# Power.net
KiCad netlist of a schematic drawn in Altium Designer
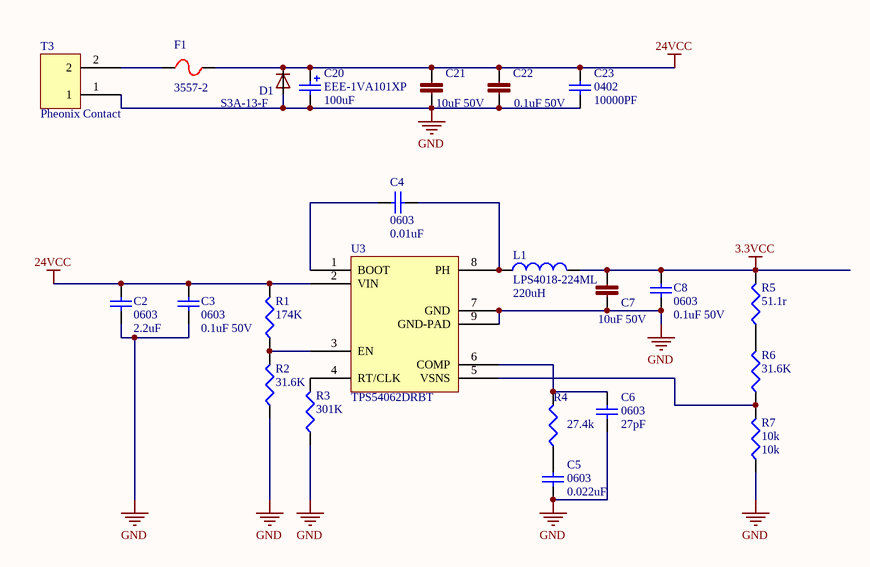
[diagram p0: Power.SchDoc]

(export (version "E")
  (design (tool "Eeschema 10.0.6"))
  (components
    (comp (ref "C2")
      (value "0603")
      (footprint "C0805")
      (description "CAP CER 2.2UF 50V 10% X5R 0805")
      (fields
        (field (name "MFR PART #") "CL21A225KB9LNNC")
        (field (name "MFR") "Samsung")
        (field (name "ALTIUM_VALUE") "2.2uF")
      )
      (libsource (lib "MongoosMini") (part "CL21A225KB9LNNC"))
    )
    (comp (ref "C3")
      (value "0603")
      (footprint "C0603")
      (description "CAP CER 0.1UF 50V 10% X7R 0603")
      (fields
        (field (name "MFR PART #") "CL10B104KB8SFNC")
        (field (name "MFR") "Samsung")
        (field (name "ALTIUM_VALUE") "0.1uF 50V")
      )
      (libsource (lib "MongoosMini") (part "CL10B104KB8SFNC"))
    )
    (comp (ref "C4")
      (value "0603")
      (footprint "C0603")
      (description "CAP CER 10000PF 50V 10% X7R 0603")
      (fields
        (field (name "MFR PART #") "CL10B103KB8NCNC")
        (field (name "MFR") "Samsung")
        (field (name "ALTIUM_VALUE") "0.01uF")
      )
      (libsource (lib "MongoosMini") (part "CL10B103KB8NCNC"))
    )
    (comp (ref "C5")
      (value "0603")
      (footprint "C0603")
      (description "CAP CER 0.022UF 50V 5% X7R 0603")
      (fields
        (field (name "MFR PART #") "CL10B223JB8NNNC")
        (field (name "MFR") "Samsung")
        (field (name "ALTIUM_VALUE") "0.022uF")
      )
      (libsource (lib "MongoosMini") (part "CL10B223JB8NNNC"))
    )
    (comp (ref "C6")
      (value "0603")
      (footprint "C0603")
      (description "CAP CER 27PF 50V 5% NP0 0603")
      (fields
        (field (name "MFR PART #") "CL10C270JB8NNNC")
        (field (name "MFR") "Samsung")
        (field (name "ALTIUM_VALUE") "27pF")
      )
      (libsource (lib "MongoosMini") (part "CL10C270JB8NNNC"))
    )
    (comp (ref "C7")
      (value "10uF 50V")
      (footprint "C1206")
      (description "CAP CER 10UF 50V 10% X5R 1206")
      (fields
        (field (name "MANUFACTURER") "Samsung")
        (field (name "MANUFACTURERPARTNUMBER") "CL31A106KBHNNNE")
        (field (name "PUBLISHER") "UltiMachine")
      )
      (libsource (lib "Tigershark3D") (part "CL31A106KBHNNNE"))
    )
    (comp (ref "C8")
      (value "0603")
      (footprint "C0603")
      (description "CAP CER 0.1UF 50V 10% X7R 0603")
      (fields
        (field (name "MFR PART #") "CL10B104KB8SFNC")
        (field (name "MFR") "Samsung")
        (field (name "ALTIUM_VALUE") "0.1uF 50V")
      )
      (libsource (lib "MongoosMini") (part "CL10B104KB8SFNC"))
    )
    (comp (ref "C20")
      (value "EEE-1VA101XP")
      (footprint "EEE-1VA101XP")
      (description "CAP ALUM 100UF 35V 20% SMD")
      (fields (field (name "DIGIKEY PART #") "PCE3951CT-ND") (field (name "ALTIUM_VALUE") "100uF"))
      (libsource (lib "Tigershark3D") (part "EEE-1VA101XP"))
    )
    (comp (ref "C21")
      (value "10uF 50V")
      (footprint "C1206")
      (description "CAP CER 10UF 50V 10% X5R 1206")
      (fields
        (field (name "MANUFACTURER") "Samsung")
        (field (name "MANUFACTURERPARTNUMBER") "CL31A106KBHNNNE")
        (field (name "PUBLISHER") "UltiMachine")
      )
      (libsource (lib "Tigershark3D") (part "CL31A106KBHNNNE"))
    )
    (comp (ref "C22")
      (value "0.1uF 50V")
      (footprint "C0603")
      (description "CAP CER 0.1UF 50V 10% X7R 0603")
      (fields
        (field (name "MANUFACTURERPARTNUMBER") "CL10B104KB8SFNC")
        (field (name "PUBLISHER") "UltiMachine")
      )
      (libsource (lib "Tigershark3D") (part "CL10B104KB8SFNC"))
    )
    (comp (ref "C23")
      (value "10000PF")
      (footprint "C0402")
      (description "CAP CER 10000PF 50V 5% X7R 0402")
      (fields
        (field (name "MANUFACTURE PART #") "CL05B103JB5NNNC")
        (field (name "MANUFACTURER") "Samsung")
        (field (name "PACKAGEREFERENCE") "0402")
        (field (name "PUBLISHER") "Ultimachine")
      )
      (libsource (lib "Tigershark3D") (part "CL05B103JB5NNNC"))
    )
    (comp (ref "D1")
      (value "S3A-13-F")
      (footprint "DO-214AB")
      (description "DIODE DO-214AB")
      (fields (field (name "PUBLISHER") "UltiMachine"))
      (libsource (lib "3Delight") (part "S3A-13-F"))
    )
    (comp (ref "F1")
      (value "3557-2")
      (footprint "3557")
      (description "FUSE PTH ATO")
      (fields (field (name "PUBLISHER") "UltiMachine"))
      (libsource (lib "3Delight") (part "3557-2"))
    )
    (comp (ref "L1")
      (value "LPS4018-224ML")
      (footprint "LPS4018-224ML")
      (description "Inductor")
      (fields
        (field (name "MFR") "Coilcraft")
        (field (name "ALTIUM_VALUE") "220uH")
        (field (name "PUBLISHER") "Altium Limited")
      )
      (libsource (lib "MongoosMini") (part "LPS4018-224ML"))
    )
    (comp (ref "R1")
      (value "174K")
      (footprint "R0603")
      (description "RES SMD 174K OHM 1% 1/10W 0603")
      (fields (field (name "MFR") "Samsung"))
      (libsource (lib "MongoosMini") (part "RC1608F1743CS"))
    )
    (comp (ref "R2")
      (value "31.6K")
      (footprint "R0603")
      (description "RES SMD 31.6K OHM 1% 1/10W 0603")
      (fields (field (name "MFR") "Samsung"))
      (libsource (lib "MongoosMini") (part "RC1608F3162CS"))
    )
    (comp (ref "R3")
      (value "301K")
      (footprint "R0603")
      (description "RES SMD 301K OHM 1% 1/10W 0603")
      (fields (field (name "MFR") "Samsung"))
      (libsource (lib "MongoosMini") (part "RC1608F3013CS"))
    )
    (comp (ref "R4")
      (value "27.4k")
      (footprint "R0603")
      (description "RES SMD 27.4K OHM 1% 1/10W 0603")
      (fields (field (name "MFR") "Samsung"))
      (libsource (lib "MongoosMini") (part "RC1608F2742CS"))
    )
    (comp (ref "R5")
      (value "51.1r")
      (footprint "R0603")
      (description "RES SMD 51.1 OHM 1% 1/10W 0603")
      (fields (field (name "MFR") "Samsung"))
      (libsource (lib "MongoosMini") (part "RC1608F51R1CS"))
    )
    (comp (ref "R6")
      (value "31.6K")
      (footprint "R0603")
      (description "RES SMD 31.6K OHM 1% 1/10W 0603")
      (fields (field (name "MFR") "Samsung"))
      (libsource (lib "MongoosMini") (part "RC1608F3162CS"))
    )
    (comp (ref "R7")
      (value "10k")
      (footprint "R0603")
      (description "RES SMD 10K OHM 5% 1/10W 0603")
      (fields (field (name "MFR") "Samsung") (field (name "ALTIUM_VALUE") "10k"))
      (libsource (lib "MongoosMini") (part "RC1608J103CS"))
    )
    (comp (ref "T3")
      (value "Pheonix Contact")
      (footprint "CON-PHEONIX-508-Alt")
      (libsource (lib "Ribbon Breakout Schem Symbols") (part "Pheonix Contact 2X1"))
    )
    (comp (ref "U3")
      (value "TPS54062DRBT")
      (footprint "QFN65P300X300X100_HS-17N")
      (description "IC REG BUCK SYNC ADJ 50MA DRBT")
      (fields (field (name "MFR") "Texas Instruments"))
      (libsource (lib "MongoosMini") (part "TPS54062DRBT"))
    )
  )
  (nets
    (net (code "1") (name "3.3VCC") (class "Default")
      (node (ref "C7") (pin "1") (pinfunction "1_1") (pintype "passive"))
      (node (ref "C8") (pin "2") (pinfunction "2_2") (pintype "passive"))
      (node (ref "L1") (pin "2") (pinfunction "2_2") (pintype "passive"))
      (node (ref "R5") (pin "2") (pinfunction "2_2") (pintype "passive"))
    )
    (net (code "2") (name "24VCC") (class "Default")
      (node (ref "C2") (pin "2") (pinfunction "2_2") (pintype "passive"))
      (node (ref "C20") (pin "1") (pinfunction "1_1") (pintype "passive"))
      (node (ref "C21") (pin "1") (pinfunction "1_1") (pintype "passive"))
      (node (ref "C22") (pin "1") (pinfunction "1_1") (pintype "passive"))
      (node (ref "C23") (pin "2") (pinfunction "2_2") (pintype "passive"))
      (node (ref "C3") (pin "2") (pinfunction "2_2") (pintype "passive"))
      (node (ref "D1") (pin "C") (pinfunction "C_C") (pintype "passive"))
      (node (ref "F1") (pin "2") (pinfunction "2_2") (pintype "passive"))
      (node (ref "R1") (pin "2") (pinfunction "2_2") (pintype "passive"))
      (node (ref "U3") (pin "2") (pinfunction "VIN_2") (pintype "passive"))
    )
    (net (code "3") (name "GND") (class "Default")
      (node (ref "C2") (pin "1") (pinfunction "1_1") (pintype "passive"))
      (node (ref "C20") (pin "2") (pinfunction "2_2") (pintype "passive"))
      (node (ref "C21") (pin "2") (pinfunction "2_2") (pintype "passive"))
      (node (ref "C22") (pin "2") (pinfunction "2_2") (pintype "passive"))
      (node (ref "C23") (pin "1") (pinfunction "1_1") (pintype "passive"))
      (node (ref "C3") (pin "1") (pinfunction "1_1") (pintype "passive"))
      (node (ref "C5") (pin "1") (pinfunction "1_1") (pintype "passive"))
      (node (ref "C6") (pin "1") (pinfunction "1_1") (pintype "passive"))
      (node (ref "C7") (pin "2") (pinfunction "2_2") (pintype "passive"))
      (node (ref "C8") (pin "1") (pinfunction "1_1") (pintype "passive"))
      (node (ref "D1") (pin "A") (pinfunction "A_A") (pintype "passive"))
      (node (ref "R2") (pin "1") (pinfunction "1_1") (pintype "passive"))
      (node (ref "R3") (pin "1") (pinfunction "1_1") (pintype "passive"))
      (node (ref "R7") (pin "1") (pinfunction "1_1") (pintype "passive"))
      (node (ref "T3") (pin "1") (pinfunction "1_1") (pintype "passive"))
      (node (ref "U3") (pin "7") (pinfunction "GND_7") (pintype "passive"))
      (node (ref "U3") (pin "9") (pinfunction "GND-PAD_9") (pintype "passive"))
    )
    (net (code "4") (name "Net-(C5-Pad2)") (class "Default")
      (node (ref "C5") (pin "2") (pinfunction "2_2") (pintype "passive"))
      (node (ref "R4") (pin "1") (pinfunction "1_1") (pintype "passive"))
    )
    (net (code "5") (name "Net-(F1-Pad1)") (class "Default")
      (node (ref "F1") (pin "1") (pinfunction "1_1") (pintype "passive"))
      (node (ref "T3") (pin "2") (pinfunction "2_2") (pintype "passive"))
    )
    (net (code "6") (name "Net-(R5-Pad1)") (class "Default")
      (node (ref "R5") (pin "1") (pinfunction "1_1") (pintype "passive"))
      (node (ref "R6") (pin "2") (pinfunction "2_2") (pintype "passive"))
    )
    (net (code "7") (name "Net-(U3-BOOT)") (class "Default")
      (node (ref "C4") (pin "2") (pinfunction "2_2") (pintype "passive"))
      (node (ref "U3") (pin "1") (pinfunction "BOOT_1") (pintype "passive"))
    )
    (net (code "8") (name "Net-(U3-COMP)") (class "Default")
      (node (ref "C6") (pin "2") (pinfunction "2_2") (pintype "passive"))
      (node (ref "R4") (pin "2") (pinfunction "2_2") (pintype "passive"))
      (node (ref "U3") (pin "6") (pinfunction "COMP_6") (pintype "passive"))
    )
    (net (code "9") (name "Net-(U3-EN)") (class "Default")
      (node (ref "R1") (pin "1") (pinfunction "1_1") (pintype "passive"))
      (node (ref "R2") (pin "2") (pinfunction "2_2") (pintype "passive"))
      (node (ref "U3") (pin "3") (pinfunction "EN_3") (pintype "passive"))
    )
    (net (code "10") (name "Net-(U3-PH)") (class "Default")
      (node (ref "C4") (pin "1") (pinfunction "1_1") (pintype "passive"))
      (node (ref "L1") (pin "1") (pinfunction "1_1") (pintype "passive"))
      (node (ref "U3") (pin "8") (pinfunction "PH_8") (pintype "passive"))
    )
    (net (code "11") (name "Net-(U3-RT{slash}CLK)") (class "Default")
      (node (ref "R3") (pin "2") (pinfunction "2_2") (pintype "passive"))
      (node (ref "U3") (pin "4") (pinfunction "RT/CLK_4") (pintype "passive"))
    )
    (net (code "12") (name "Net-(U3-VSNS)") (class "Default")
      (node (ref "R6") (pin "1") (pinfunction "1_1") (pintype "passive"))
      (node (ref "R7") (pin "2") (pinfunction "2_2") (pintype "passive"))
      (node (ref "U3") (pin "5") (pinfunction "VSNS_5") (pintype "passive"))
    )
  )
)
